# FDTI-UPDI_adapter.net
KiCad netlist of a schematic drawn in EAGLE
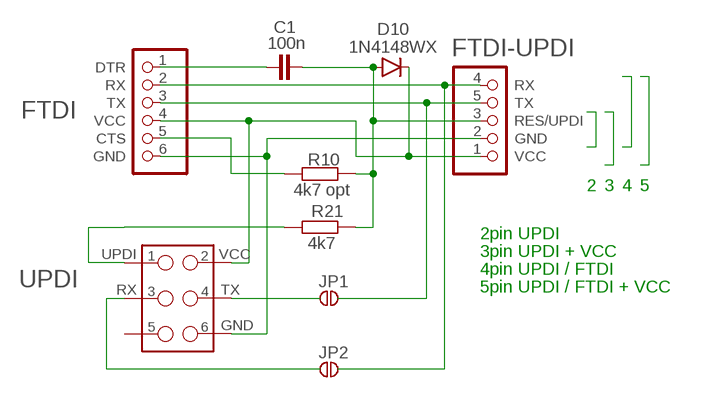
[diagram p0: schematic, sheet 1]

(export (version "E")
  (design (tool "Eeschema 10.0.6"))
  (components
    (comp (ref "C1")
      (value "100n")
      (footprint "eagle-import:0603-SMALL")
      (libsource (lib "eagle-import") (part "SMD-C-0603-SMALL"))
    )
    (comp (ref "D10")
      (value "1N4148WX")
      (footprint "eagle-import:SOD-323")
      (libsource (lib "eagle-import") (part "DIODE-SMD"))
    )
    (comp (ref "J2")
      (value "FTDI")
      (footprint "eagle-import:ZIGZAG-FTDI")
      (libsource (lib "eagle-import") (part "FTDI"))
    )
    (comp (ref "J100")
      (value "FTDI-UPDI")
      (footprint "eagle-import:FTDI-UPDI-ZIGZAG")
      (libsource (lib "eagle-import") (part "FTDI-UPDI"))
    )
    (comp (ref "JP1")
      (value "JUMPER_SJSMALL")
      (footprint "eagle-import:SJ_2S-NO-NS")
      (libsource (lib "eagle-import") (part "JUMPER_SJSMALL"))
    )
    (comp (ref "JP2")
      (value "JUMPER_SJSMALL")
      (footprint "eagle-import:SJ_2S-NO-NS")
      (libsource (lib "eagle-import") (part "JUMPER_SJSMALL"))
    )
    (comp (ref "R10")
      (value "4k7 opt")
      (footprint "eagle-import:0603-SMALL")
      (libsource (lib "eagle-import") (part "SMD-R-0603-SMALL"))
    )
    (comp (ref "R21")
      (value "4k7")
      (footprint "eagle-import:0603-SMALL")
      (libsource (lib "eagle-import") (part "SMD-R-0603-SMALL"))
    )
    (comp (ref "UPDI")
      (value "M3X2\"")
      (footprint "eagle-import:2X3_TEST_POINTS")
      (libsource (lib "eagle-import") (part "M3X2{dblquote}"))
    )
  )
  (nets
    (net (code "1") (name "/GND") (class "Default")
      (node (ref "J100") (pin "2") (pinfunction "GND_2") (pintype "passive"))
      (node (ref "J2") (pin "6") (pinfunction "GND_6") (pintype "passive"))
      (node (ref "UPDI") (pin "6") (pinfunction "6_6") (pintype "bidirectional"))
    )
    (net (code "2") (name "/RX") (class "Default")
      (node (ref "JP2") (pin "2") (pinfunction "2_2") (pintype "passive"))
      (node (ref "UPDI") (pin "3") (pinfunction "3_3") (pintype "bidirectional"))
    )
    (net (code "3") (name "/TX") (class "Default")
      (node (ref "JP1") (pin "2") (pinfunction "2_2") (pintype "passive"))
      (node (ref "UPDI") (pin "4") (pinfunction "4_4") (pintype "bidirectional"))
    )
    (net (code "4") (name "/UPDI") (class "Default")
      (node (ref "R21") (pin "2") (pinfunction "2_2") (pintype "passive"))
      (node (ref "UPDI") (pin "1") (pinfunction "1_1") (pintype "bidirectional"))
    )
    (net (code "5") (name "/VCC") (class "Default")
      (node (ref "D10") (pin "C") (pinfunction "C_C") (pintype "passive"))
      (node (ref "J100") (pin "1") (pinfunction "VCC_1") (pintype "passive"))
      (node (ref "J2") (pin "4") (pinfunction "VCC_4") (pintype "passive"))
      (node (ref "UPDI") (pin "2") (pinfunction "2_2") (pintype "bidirectional"))
    )
    (net (code "6") (name "Net-(J2-CTS)") (class "Default")
      (node (ref "J2") (pin "5") (pinfunction "CTS_5") (pintype "passive"))
      (node (ref "R10") (pin "2") (pinfunction "2_2") (pintype "passive"))
    )
    (net (code "7") (name "Net-(J2-DTR)") (class "Default")
      (node (ref "C1") (pin "1") (pinfunction "1_1") (pintype "passive"))
      (node (ref "J2") (pin "1") (pinfunction "DTR_1") (pintype "passive"))
    )
    (net (code "8") (name "Net-(J100-RES{slash}UPDI)") (class "Default")
      (node (ref "C1") (pin "2") (pinfunction "2_2") (pintype "passive"))
      (node (ref "D10") (pin "A") (pinfunction "A_A") (pintype "passive"))
      (node (ref "J100") (pin "3") (pinfunction "RES/UPDI_3") (pintype "passive"))
      (node (ref "R10") (pin "1") (pinfunction "1_1") (pintype "passive"))
      (node (ref "R21") (pin "1") (pinfunction "1_1") (pintype "passive"))
    )
    (net (code "9") (name "Net-(J100-RX)") (class "Default")
      (node (ref "J100") (pin "4") (pinfunction "RX_4") (pintype "passive"))
      (node (ref "J2") (pin "2") (pinfunction "RX_2") (pintype "passive"))
      (node (ref "JP2") (pin "1") (pinfunction "1_1") (pintype "passive"))
    )
    (net (code "10") (name "Net-(J100-TX)") (class "Default")
      (node (ref "J100") (pin "5") (pinfunction "TX_5") (pintype "passive"))
      (node (ref "J2") (pin "3") (pinfunction "TX_3") (pintype "passive"))
      (node (ref "JP1") (pin "1") (pinfunction "1_1") (pintype "passive"))
    )
    (net (code "11") (name "unconnected-(UPDI-Pad5)") (class "Default")
      (node (ref "UPDI") (pin "5") (pinfunction "5_5") (pintype "bidirectional"))
    )
  )
)
